# POWER_1_8V_3A.net
KiCad netlist of a schematic drawn in Altium Designer
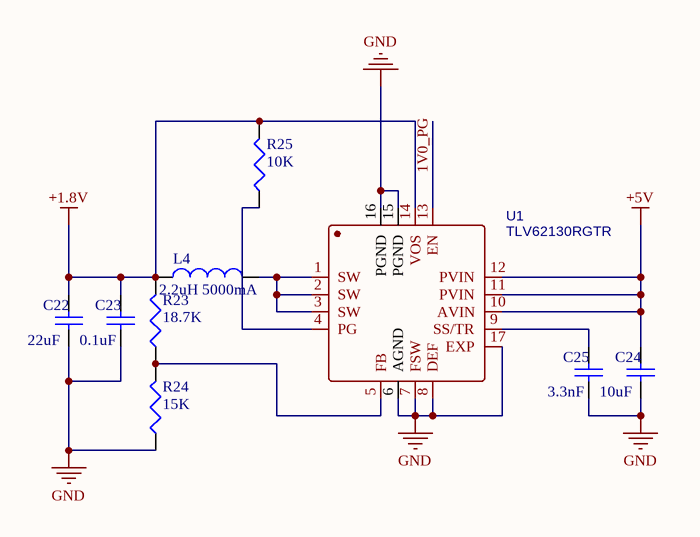
[diagram p0: POWER_1.8V_3A.SchDoc]

(export (version "E")
  (design (tool "Eeschema 10.0.6"))
  (components
    (comp (ref "C22")
      (value "22uF")
      (footprint "C1210")
      (description "Capacitor (Semiconductor SIM Model)")
      (fields (field (name "Comment") "Cap Semi") (field (name "PUBLISHER") "Altium Limited"))
      (libsource (lib "Miscellaneous Devices") (part "Cap Semi"))
    )
    (comp (ref "C23")
      (value "0.1uF")
      (footprint "C1210")
      (description "Capacitor (Semiconductor SIM Model)")
      (fields (field (name "Comment") "Cap Semi") (field (name "PUBLISHER") "Altium Limited"))
      (libsource (lib "Miscellaneous Devices") (part "Cap Semi"))
    )
    (comp (ref "C24")
      (value "10uF")
      (footprint "C1210")
      (description "Capacitor (Semiconductor SIM Model)")
      (fields (field (name "Comment") "Cap Semi") (field (name "PUBLISHER") "Altium Limited"))
      (libsource (lib "Miscellaneous Devices") (part "Cap Semi"))
    )
    (comp (ref "C25")
      (value "3.3nF")
      (footprint "C1210")
      (description "Capacitor (Semiconductor SIM Model)")
      (fields (field (name "Comment") "Cap Semi") (field (name "PUBLISHER") "Altium Limited"))
      (libsource (lib "Miscellaneous Devices") (part "Cap Semi"))
    )
    (comp (ref "L4")
      (value "2.2uH 5000mA")
      (footprint "IND-SMD_L5.5-W5.2")
      (description "Inductor")
      (fields (field (name "PUBLISHER") "Altium Limited"))
      (libsource (lib "Miscellaneous Devices") (part "Inductor"))
    )
    (comp (ref "R23")
      (value "18.7K")
      (footprint "J1-0603")
      (description "Resistor")
      (fields (field (name "Comment") "Res3") (field (name "PUBLISHER") "Altium Limited"))
      (libsource (lib "Miscellaneous Devices") (part "Res3"))
    )
    (comp (ref "R24")
      (value "15K")
      (footprint "J1-0603")
      (description "Resistor")
      (fields (field (name "Comment") "Res3") (field (name "PUBLISHER") "Altium Limited"))
      (libsource (lib "Miscellaneous Devices") (part "Res3"))
    )
    (comp (ref "R25")
      (value "10K")
      (footprint "J1-0603")
      (description "Resistor")
      (fields (field (name "Comment") "Res3") (field (name "PUBLISHER") "Altium Limited"))
      (libsource (lib "Miscellaneous Devices") (part "Res3"))
    )
    (comp (ref "U1")
      (value "TLV62130RGTR")
      (footprint "QFN-16")
      (fields (field (name "BOM_SUPPLIER PART") "C122479") (field (name "CONTRIBUTOR") "LCSC"))
      (libsource (lib "power_chip") (part "TLV62130RGTR"))
    )
  )
  (nets
    (net (code "1") (name "+1.8V") (class "Default")
      (node (ref "C22") (pin "2") (pinfunction "2_2") (pintype "passive"))
      (node (ref "C23") (pin "2") (pinfunction "2_2") (pintype "passive"))
      (node (ref "L4") (pin "1") (pinfunction "1_1") (pintype "passive"))
      (node (ref "R23") (pin "2") (pinfunction "2_2") (pintype "passive"))
      (node (ref "R25") (pin "2") (pinfunction "2_2") (pintype "passive"))
      (node (ref "U1") (pin "14") (pinfunction "VOS_14") (pintype "passive"))
    )
    (net (code "2") (name "+5V") (class "Default")
      (node (ref "C24") (pin "2") (pinfunction "2_2") (pintype "passive"))
      (node (ref "U1") (pin "10") (pinfunction "AVIN_10") (pintype "passive"))
      (node (ref "U1") (pin "11") (pinfunction "PVIN_11") (pintype "passive"))
      (node (ref "U1") (pin "12") (pinfunction "PVIN_12") (pintype "passive"))
    )
    (net (code "3") (name "/1V0_PG") (class "Default")
      (node (ref "U1") (pin "13") (pinfunction "EN_13") (pintype "passive"))
    )
    (net (code "4") (name "GND") (class "Default")
      (node (ref "C22") (pin "1") (pinfunction "1_1") (pintype "passive"))
      (node (ref "C23") (pin "1") (pinfunction "1_1") (pintype "passive"))
      (node (ref "C24") (pin "1") (pinfunction "1_1") (pintype "passive"))
      (node (ref "C25") (pin "1") (pinfunction "1_1") (pintype "passive"))
      (node (ref "R24") (pin "1") (pinfunction "1_1") (pintype "passive"))
      (node (ref "U1") (pin "15") (pinfunction "PGND_15") (pintype "passive"))
      (node (ref "U1") (pin "16") (pinfunction "PGND_16") (pintype "passive"))
      (node (ref "U1") (pin "17") (pinfunction "EXP_17") (pintype "passive"))
      (node (ref "U1") (pin "6") (pinfunction "AGND_6") (pintype "passive"))
      (node (ref "U1") (pin "7") (pinfunction "FSW_7") (pintype "passive"))
      (node (ref "U1") (pin "8") (pinfunction "DEF_8") (pintype "passive"))
    )
    (net (code "5") (name "Net-(L4-Pad2)") (class "Default")
      (node (ref "L4") (pin "2") (pinfunction "2_2") (pintype "passive"))
      (node (ref "U1") (pin "1") (pinfunction "SW_1") (pintype "passive"))
      (node (ref "U1") (pin "2") (pinfunction "SW_2") (pintype "passive"))
      (node (ref "U1") (pin "3") (pinfunction "SW_3") (pintype "passive"))
    )
    (net (code "6") (name "Net-(U1-FB)") (class "Default")
      (node (ref "R23") (pin "1") (pinfunction "1_1") (pintype "passive"))
      (node (ref "R24") (pin "2") (pinfunction "2_2") (pintype "passive"))
      (node (ref "U1") (pin "5") (pinfunction "FB_5") (pintype "passive"))
    )
    (net (code "7") (name "Net-(U1-PG)") (class "Default")
      (node (ref "R25") (pin "1") (pinfunction "1_1") (pintype "passive"))
      (node (ref "U1") (pin "4") (pinfunction "PG_4") (pintype "passive"))
    )
    (net (code "8") (name "Net-(U1-SS{slash}TR)") (class "Default")
      (node (ref "C25") (pin "2") (pinfunction "2_2") (pintype "passive"))
      (node (ref "U1") (pin "9") (pinfunction "SS/TR_9") (pintype "passive"))
    )
  )
)
